# Power.net
KiCad netlist of a schematic drawn in Altium Designer
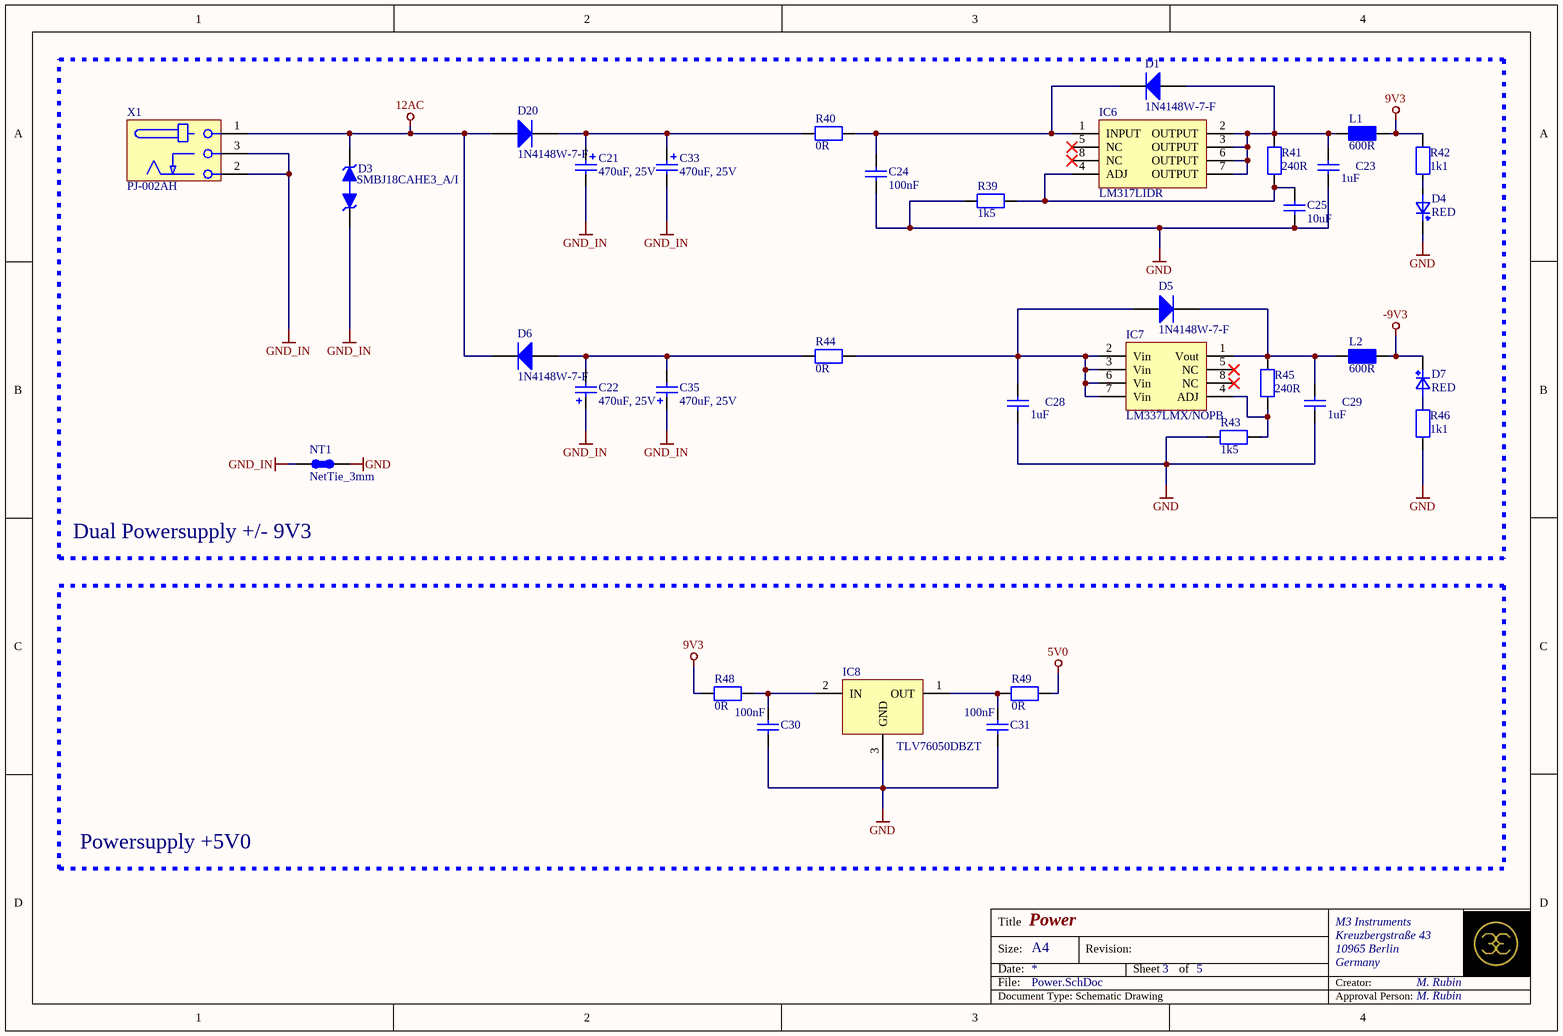
[diagram p0: Power.SchDoc]

(export (version "E")
  (design (tool "Eeschema 10.0.6"))
  (components
    (comp (ref "C21")
      (value "470uF, 25V")
      (footprint "WCAP-ATG8_D8H11.5")
      (description "WCAP-ATG8 Aluminum Electrolytic Capacitor, Radial, THT, D8xH11.5, 470uF, 25V")
      (fields
        (field (name "MANUFACTURER") "Wurth Elektronik")
        (field (name "MANUFACTURER PART NUMBER") "860010474013")
      )
      (libsource (lib "Caps") (part "CAP_470uF, 25V"))
    )
    (comp (ref "C22")
      (value "470uF, 25V")
      (footprint "WCAP-ATG8_D8H11.5")
      (description "WCAP-ATG8 Aluminum Electrolytic Capacitor, Radial, THT, D8xH11.5, 470uF, 25V")
      (fields
        (field (name "MANUFACTURER") "Wurth Elektronik")
        (field (name "MANUFACTURER PART NUMBER") "860010474013")
      )
      (libsource (lib "Caps") (part "CAP_470uF, 25V"))
    )
    (comp (ref "C23")
      (value "1uF")
      (footprint "CAPC2012X145N")
      (description "Multilayer Ceramic Capacitors MLCC - SMD/SMT, 1uF")
      (fields
        (field (name "MANUFACTURER") "Samsung Electro-Mechanics")
        (field (name "MANUFACTURER PART NUMBER") "CL21B105KBFNNNE")
      )
      (libsource (lib "Caps") (part "CAP_1uF_0805"))
    )
    (comp (ref "C24")
      (value "100nF")
      (footprint "CAPC1608X95N")
      (description "Multilayer Ceramic Capacitors MLCC - SMD/SMT, 100nF")
      (fields
        (field (name "MANUFACTURER") "YAGEO")
        (field (name "MANUFACTURER PART NUMBER") "CC0603KRX7R9BB104")
      )
      (libsource (lib "Caps") (part "CAP_100nF_0603"))
    )
    (comp (ref "C25")
      (value "10uF")
      (footprint "CAPC2012X145N")
      (description "Multilayer Ceramic Capacitors MLCC - SMD/SMT, 10uF")
      (fields
        (field (name "MANUFACTURER") "Samsung Electro-Mechanics")
        (field (name "MANUFACTURER PART NUMBER") "CL21A106KAYNNNE")
      )
      (libsource (lib "Caps") (part "CAP_10uF_0805"))
    )
    (comp (ref "C28")
      (value "1uF")
      (footprint "CAPC2012X145N")
      (description "Multilayer Ceramic Capacitors MLCC - SMD/SMT, 1uF")
      (fields
        (field (name "MANUFACTURER") "Samsung Electro-Mechanics")
        (field (name "MANUFACTURER PART NUMBER") "CL21B105KBFNNNE")
      )
      (libsource (lib "Caps") (part "CAP_1uF_0805"))
    )
    (comp (ref "C29")
      (value "1uF")
      (footprint "CAPC2012X145N")
      (description "Multilayer Ceramic Capacitors MLCC - SMD/SMT, 1uF")
      (fields
        (field (name "MANUFACTURER") "Samsung Electro-Mechanics")
        (field (name "MANUFACTURER PART NUMBER") "CL21B105KBFNNNE")
      )
      (libsource (lib "Caps") (part "CAP_1uF_0805"))
    )
    (comp (ref "C30")
      (value "100nF")
      (footprint "CAPC1608X95N")
      (description "Multilayer Ceramic Capacitors MLCC - SMD/SMT, 100nF")
      (fields
        (field (name "MANUFACTURER") "YAGEO")
        (field (name "MANUFACTURER PART NUMBER") "CC0603KRX7R9BB104")
      )
      (libsource (lib "Caps") (part "CAP_100nF_0603"))
    )
    (comp (ref "C31")
      (value "100nF")
      (footprint "CAPC1608X95N")
      (description "Multilayer Ceramic Capacitors MLCC - SMD/SMT, 100nF")
      (fields
        (field (name "MANUFACTURER") "YAGEO")
        (field (name "MANUFACTURER PART NUMBER") "CC0603KRX7R9BB104")
      )
      (libsource (lib "Caps") (part "CAP_100nF_0603"))
    )
    (comp (ref "C33")
      (value "470uF, 25V")
      (footprint "WCAP-ATG8_D8H11.5")
      (description "WCAP-ATG8 Aluminum Electrolytic Capacitor, Radial, THT, D8xH11.5, 470uF, 25V")
      (fields
        (field (name "MANUFACTURER") "Wurth Elektronik")
        (field (name "MANUFACTURER PART NUMBER") "860010474013")
      )
      (libsource (lib "Caps") (part "CAP_470uF, 25V"))
    )
    (comp (ref "C35")
      (value "470uF, 25V")
      (footprint "WCAP-ATG8_D8H11.5")
      (description "WCAP-ATG8 Aluminum Electrolytic Capacitor, Radial, THT, D8xH11.5, 470uF, 25V")
      (fields
        (field (name "MANUFACTURER") "Wurth Elektronik")
        (field (name "MANUFACTURER PART NUMBER") "860010474013")
      )
      (libsource (lib "Caps") (part "CAP_470uF, 25V"))
    )
    (comp (ref "D1")
      (value "1N4148W-7-F")
      (footprint "SOD-123")
      (description "Diodes - General Purpose, Power, Switching SURFACE MOUNT FAST SWITCHING DIODE 2A")
      (fields (field (name "MANUFACTURER") "Diodes Incorporated"))
      (libsource (lib "Diodes") (part "1N4148W-7-F"))
    )
    (comp (ref "D3")
      (value "SMBJ18CAHE3_A/I")
      (footprint "DIOM4336X24N")
      (description "ESD Suppressors / TVS Diodes 600W 18V 5% SMB (DO-214AA)")
      (fields (field (name "MANUFACTURER") "Vishay General Semiconductor"))
      (libsource (lib "Diodes") (part "DIO_SMBJ18CAHE3_A/I"))
    )
    (comp (ref "D4")
      (value "RED")
      (footprint "WL-SMCW_0805")
      (description "Standard LEDs - SMD WL-SMCW SMDMono TpVw Waterclr 0805 Red")
      (fields
        (field (name "MANUFACTURER") "Wurth Elektronik")
        (field (name "MANUFACTURER PART NUMBER") "150080RS75000")
      )
      (libsource (lib "Diodes") (part "LED_0805_RED_AK"))
    )
    (comp (ref "D5")
      (value "1N4148W-7-F")
      (footprint "SOD-123")
      (description "Diodes - General Purpose, Power, Switching SURFACE MOUNT FAST SWITCHING DIODE 2A")
      (fields (field (name "MANUFACTURER") "Diodes Incorporated"))
      (libsource (lib "Diodes") (part "1N4148W-7-F"))
    )
    (comp (ref "D6")
      (value "1N4148W-7-F")
      (footprint "SOD-123")
      (description "Diodes - General Purpose, Power, Switching SURFACE MOUNT FAST SWITCHING DIODE 2A")
      (fields (field (name "MANUFACTURER") "Diodes Incorporated"))
      (libsource (lib "Diodes") (part "1N4148W-7-F"))
    )
    (comp (ref "D7")
      (value "RED")
      (footprint "WL-SMCW_0805")
      (description "Standard LEDs - SMD WL-SMCW SMDMono TpVw Waterclr 0805 Red")
      (fields
        (field (name "MANUFACTURER") "Wurth Elektronik")
        (field (name "MANUFACTURER PART NUMBER") "150080RS75000")
      )
      (libsource (lib "Diodes") (part "LED_0805_RED_AK"))
    )
    (comp (ref "D20")
      (value "1N4148W-7-F")
      (footprint "SOD-123")
      (description "Diodes - General Purpose, Power, Switching SURFACE MOUNT FAST SWITCHING DIODE 2A")
      (fields (field (name "MANUFACTURER") "Diodes Incorporated"))
      (libsource (lib "Diodes") (part "1N4148W-7-F"))
    )
    (comp (ref "IC6")
      (value "LM317LIDR")
      (footprint "SOIC127P600X175-8N")
      (description "Linear Voltage Regulators")
      (fields (field (name "MANUFACTURER") "Texas Instruments"))
      (libsource (lib "ICs") (part "IC_LM317LIDR"))
    )
    (comp (ref "IC7")
      (value "LM337LMX/NOPB")
      (footprint "SOIC127P600X175-8N")
      (description "IC REG LIN POS ADJ 300MA SOT25")
      (fields (field (name "MANUFACTURER") "Texas Instruments"))
      (libsource (lib "ICs") (part "IC_LM337LMX/NOPB"))
    )
    (comp (ref "IC8")
      (value "TLV76050DBZT")
      (footprint "SOT95P280X135-3N_123")
      (description "PMIC - Spannungsregler - Linear Positiv Fest 1 Ausgang 100mA SOT-23-3")
      (fields (field (name "MANUFACTURER") "Texas Instruments"))
      (libsource (lib "ICs") (part "IC_TLV76050DBZT"))
    )
    (comp (ref "L1")
      (value "600R")
      (footprint "INDC2012X85N")
      (description "Ferrite Beads 0805 600 OHM")
      (fields
        (field (name "MANUFACTURER") "Murata Electronics")
        (field (name "MANUFACTURER PART NUMBER") "BLM21AG601SN1D")
      )
      (libsource (lib "Inductors") (part "FB_600R_600mA_0805"))
    )
    (comp (ref "L2")
      (value "600R")
      (footprint "INDC2012X85N")
      (description "Ferrite Beads 0805 600 OHM")
      (fields
        (field (name "MANUFACTURER") "Murata Electronics")
        (field (name "MANUFACTURER PART NUMBER") "BLM21AG601SN1D")
      )
      (libsource (lib "Inductors") (part "FB_600R_600mA_0805"))
    )
    (comp (ref "NT1")
      (value "NetTie_3mm")
      (footprint "NET_TIE_3MM")
      (description "3mm NetTie")
      (libsource (lib "MISC") (part "NetTie_3mm"))
    )
    (comp (ref "R39")
      (value "1k5")
      (footprint "RESC2012X70N")
      (description "Thick Film Resistors - SMD 1.5 kOhms 125 mW 0805 1% AEC-Q200")
      (fields
        (field (name "MANUFACTURER") "YAGEO")
        (field (name "MANUFACTURER PART NUMBER") "AC0805FR-071K5L")
      )
      (libsource (lib "Resistors") (part "RES_1k5_0805"))
    )
    (comp (ref "R40")
      (value "0R")
      (footprint "RESC2012X70N")
      (description "Thick Film Resistors - SMD 1/8watt ZEROohm Jumper")
      (fields
        (field (name "MANUFACTURER") "Vishay")
        (field (name "MANUFACTURER PART NUMBER") "CRCW08050000Z0EA")
      )
      (libsource (lib "Resistors") (part "RES_0R_0805"))
    )
    (comp (ref "R41")
      (value "240R")
      (footprint "RESC2012X70N")
      (description "Thick Film Resistors - SMD 1/8watt 240ohms 1%")
      (fields
        (field (name "MANUFACTURER") "Vishay / Dale")
        (field (name "MANUFACTURER PART NUMBER") "CRCW0805240RFKEA")
      )
      (libsource (lib "Resistors") (part "RES_240R_0805"))
    )
    (comp (ref "R42")
      (value "1k1")
      (footprint "RESC2012X70N")
      (description "Thick Film Resistors - SMD 1/8watt 1.1Kohms 1% 100ppm")
      (fields
        (field (name "MANUFACTURER") "Vishay / Dale")
        (field (name "MANUFACTURER PART NUMBER") "CRCW08051K10FKEA")
      )
      (libsource (lib "") (part "RES_1k1_0805_1"))
    )
    (comp (ref "R43")
      (value "1k5")
      (footprint "RESC2012X70N")
      (description "Thick Film Resistors - SMD 1.5 kOhms 125 mW 0805 1% AEC-Q200")
      (fields
        (field (name "MANUFACTURER") "YAGEO")
        (field (name "MANUFACTURER PART NUMBER") "AC0805FR-071K5L")
      )
      (libsource (lib "Resistors") (part "RES_1k5_0805"))
    )
    (comp (ref "R44")
      (value "0R")
      (footprint "RESC2012X70N")
      (description "Thick Film Resistors - SMD 1/8watt ZEROohm Jumper")
      (fields
        (field (name "MANUFACTURER") "Vishay")
        (field (name "MANUFACTURER PART NUMBER") "CRCW08050000Z0EA")
      )
      (libsource (lib "Resistors") (part "RES_0R_0805"))
    )
    (comp (ref "R45")
      (value "240R")
      (footprint "RESC2012X70N")
      (description "Thick Film Resistors - SMD 1/8watt 240ohms 1%")
      (fields
        (field (name "MANUFACTURER") "Vishay / Dale")
        (field (name "MANUFACTURER PART NUMBER") "CRCW0805240RFKEA")
      )
      (libsource (lib "Resistors") (part "RES_240R_0805"))
    )
    (comp (ref "R46")
      (value "1k1")
      (footprint "RESC2012X70N")
      (description "Thick Film Resistors - SMD 1/8watt 1.1Kohms 1% 100ppm")
      (fields
        (field (name "MANUFACTURER") "Vishay / Dale")
        (field (name "MANUFACTURER PART NUMBER") "CRCW08051K10FKEA")
      )
      (libsource (lib "Resistors") (part "RES_1k1_0805"))
    )
    (comp (ref "R48")
      (value "0R")
      (footprint "RESC2012X70N")
      (description "Thick Film Resistors - SMD 1/8watt ZEROohm Jumper")
      (fields
        (field (name "MANUFACTURER") "Vishay")
        (field (name "MANUFACTURER PART NUMBER") "CRCW08050000Z0EA")
      )
      (libsource (lib "Resistors") (part "RES_0R_0805"))
    )
    (comp (ref "R49")
      (value "0R")
      (footprint "RESC2012X70N")
      (description "Thick Film Resistors - SMD 1/8watt ZEROohm Jumper")
      (fields
        (field (name "MANUFACTURER") "Vishay")
        (field (name "MANUFACTURER PART NUMBER") "CRCW08050000Z0EA")
      )
      (libsource (lib "Resistors") (part "RES_0R_0805"))
    )
    (comp (ref "X1")
      (value "PJ-002AH")
      (footprint "PJ3L1400H110")
      (description "DC Power Connectors Power Jacks, Inside Contact Diameter 2mm, Outside Contact Diameter 6,5mm")
      (fields
        (field (name "MANUFACTURER") "CUI Devices")
        (field (name "LUMIRA PART NUMBER") "S-QMS-SPEC-32532")
      )
      (libsource (lib "_CONNECTORS") (part "PJ-002AH"))
    )
  )
  (nets
    (net (code "1") (name "-9V3") (class "Default")
      (node (ref "D7") (pin "K") (pinfunction "K_K") (pintype "passive"))
      (node (ref "L2") (pin "2") (pinfunction "2_2") (pintype "passive"))
    )
    (net (code "2") (name "5V0") (class "Default")
      (node (ref "R49") (pin "2") (pinfunction "2_2") (pintype "passive"))
    )
    (net (code "3") (name "9V3") (class "Default")
      (node (ref "L1") (pin "2") (pinfunction "2_2") (pintype "passive"))
      (node (ref "R42") (pin "2") (pinfunction "2_2") (pintype "passive"))
      (node (ref "R48") (pin "1") (pinfunction "1_1") (pintype "passive"))
    )
    (net (code "4") (name "12AC") (class "Default")
      (node (ref "D20") (pin "1") (pinfunction "A_1") (pintype "passive"))
      (node (ref "D3") (pin "K") (pinfunction "K_K") (pintype "passive"))
      (node (ref "D6") (pin "2") (pinfunction "K_2") (pintype "passive"))
      (node (ref "X1") (pin "1") (pinfunction "1_1") (pintype "passive"))
    )
    (net (code "5") (name "GND") (class "Default")
      (node (ref "C23") (pin "1") (pinfunction "1_1") (pintype "passive"))
      (node (ref "C24") (pin "1") (pinfunction "1_1") (pintype "passive"))
      (node (ref "C25") (pin "1") (pinfunction "1_1") (pintype "passive"))
      (node (ref "C28") (pin "1") (pinfunction "1_1") (pintype "passive"))
      (node (ref "C29") (pin "1") (pinfunction "1_1") (pintype "passive"))
      (node (ref "C30") (pin "1") (pinfunction "1_1") (pintype "passive"))
      (node (ref "C31") (pin "1") (pinfunction "1_1") (pintype "passive"))
      (node (ref "D4") (pin "K") (pinfunction "K_K") (pintype "passive"))
      (node (ref "IC8") (pin "3") (pinfunction "GND_3") (pintype "power_in"))
      (node (ref "NT1") (pin "1") (pinfunction "1_1") (pintype "passive"))
      (node (ref "R39") (pin "1") (pinfunction "1_1") (pintype "passive"))
      (node (ref "R43") (pin "1") (pinfunction "1_1") (pintype "passive"))
      (node (ref "R46") (pin "2") (pinfunction "2_2") (pintype "passive"))
    )
    (net (code "6") (name "GND_IN") (class "Default")
      (node (ref "C21") (pin "N") (pinfunction "N_N") (pintype "passive"))
      (node (ref "C22") (pin "P") (pinfunction "P_P") (pintype "passive"))
      (node (ref "C33") (pin "N") (pinfunction "N_N") (pintype "passive"))
      (node (ref "C35") (pin "P") (pinfunction "P_P") (pintype "passive"))
      (node (ref "D3") (pin "A") (pinfunction "A_A") (pintype "passive"))
      (node (ref "NT1") (pin "2") (pinfunction "2_2") (pintype "passive"))
      (node (ref "X1") (pin "2") (pinfunction "2_2") (pintype "passive"))
      (node (ref "X1") (pin "3") (pinfunction "3_3") (pintype "passive"))
    )
    (net (code "7") (name "Net-(D1-A)") (class "Default")
      (node (ref "C23") (pin "2") (pinfunction "2_2") (pintype "passive"))
      (node (ref "D1") (pin "1") (pinfunction "A_1") (pintype "passive"))
      (node (ref "IC6") (pin "2") (pinfunction "OUTPUT_2") (pintype "power_in"))
      (node (ref "IC6") (pin "3") (pinfunction "OUTPUT_3") (pintype "power_in"))
      (node (ref "IC6") (pin "6") (pinfunction "OUTPUT_6") (pintype "power_in"))
      (node (ref "IC6") (pin "7") (pinfunction "OUTPUT_7") (pintype "power_in"))
      (node (ref "L1") (pin "1") (pinfunction "1_1") (pintype "passive"))
      (node (ref "R41") (pin "2") (pinfunction "2_2") (pintype "passive"))
    )
    (net (code "8") (name "Net-(D1-K)") (class "Default")
      (node (ref "C24") (pin "2") (pinfunction "2_2") (pintype "passive"))
      (node (ref "D1") (pin "2") (pinfunction "K_2") (pintype "passive"))
      (node (ref "IC6") (pin "1") (pinfunction "INPUT_1") (pintype "passive"))
      (node (ref "R40") (pin "2") (pinfunction "2_2") (pintype "passive"))
    )
    (net (code "9") (name "Net-(D4-PadA)") (class "Default")
      (node (ref "D4") (pin "A") (pinfunction "A_A") (pintype "passive"))
      (node (ref "R42") (pin "1") (pinfunction "1_1") (pintype "passive"))
    )
    (net (code "10") (name "Net-(D5-A)") (class "Default")
      (node (ref "C28") (pin "2") (pinfunction "2_2") (pintype "passive"))
      (node (ref "D5") (pin "1") (pinfunction "A_1") (pintype "passive"))
      (node (ref "IC7") (pin "2") (pinfunction "Vin_2") (pintype "power_in"))
      (node (ref "IC7") (pin "3") (pinfunction "Vin_3") (pintype "power_in"))
      (node (ref "IC7") (pin "6") (pinfunction "Vin_6") (pintype "power_in"))
      (node (ref "IC7") (pin "7") (pinfunction "Vin_7") (pintype "power_in"))
      (node (ref "R44") (pin "2") (pinfunction "2_2") (pintype "passive"))
    )
    (net (code "11") (name "Net-(D5-K)") (class "Default")
      (node (ref "C29") (pin "2") (pinfunction "2_2") (pintype "passive"))
      (node (ref "D5") (pin "2") (pinfunction "K_2") (pintype "passive"))
      (node (ref "IC7") (pin "1") (pinfunction "Vout_1") (pintype "passive"))
      (node (ref "L2") (pin "1") (pinfunction "1_1") (pintype "passive"))
      (node (ref "R45") (pin "2") (pinfunction "2_2") (pintype "passive"))
    )
    (net (code "12") (name "Net-(D6-A)") (class "Default")
      (node (ref "C22") (pin "N") (pinfunction "N_N") (pintype "passive"))
      (node (ref "C35") (pin "N") (pinfunction "N_N") (pintype "passive"))
      (node (ref "D6") (pin "1") (pinfunction "A_1") (pintype "passive"))
      (node (ref "R44") (pin "1") (pinfunction "1_1") (pintype "passive"))
    )
    (net (code "13") (name "Net-(D7-PadA)") (class "Default")
      (node (ref "D7") (pin "A") (pinfunction "A_A") (pintype "passive"))
      (node (ref "R46") (pin "1") (pinfunction "1_1") (pintype "passive"))
    )
    (net (code "14") (name "Net-(D20-K)") (class "Default")
      (node (ref "C21") (pin "P") (pinfunction "P_P") (pintype "passive"))
      (node (ref "C33") (pin "P") (pinfunction "P_P") (pintype "passive"))
      (node (ref "D20") (pin "2") (pinfunction "K_2") (pintype "passive"))
      (node (ref "R40") (pin "1") (pinfunction "1_1") (pintype "passive"))
    )
    (net (code "15") (name "Net-(IC6-ADJ)") (class "Default")
      (node (ref "C25") (pin "2") (pinfunction "2_2") (pintype "passive"))
      (node (ref "IC6") (pin "4") (pinfunction "ADJ_4") (pintype "power_in"))
      (node (ref "R39") (pin "2") (pinfunction "2_2") (pintype "passive"))
      (node (ref "R41") (pin "1") (pinfunction "1_1") (pintype "passive"))
    )
    (net (code "16") (name "Net-(IC7-ADJ)") (class "Default")
      (node (ref "IC7") (pin "4") (pinfunction "ADJ_4") (pintype "power_in"))
      (node (ref "R43") (pin "2") (pinfunction "2_2") (pintype "passive"))
      (node (ref "R45") (pin "1") (pinfunction "1_1") (pintype "passive"))
    )
    (net (code "17") (name "Net-(IC8-IN)") (class "Default")
      (node (ref "C30") (pin "2") (pinfunction "2_2") (pintype "passive"))
      (node (ref "IC8") (pin "2") (pinfunction "IN_2") (pintype "power_in"))
      (node (ref "R48") (pin "2") (pinfunction "2_2") (pintype "passive"))
    )
    (net (code "18") (name "Net-(IC8-OUT)") (class "Default")
      (node (ref "C31") (pin "2") (pinfunction "2_2") (pintype "passive"))
      (node (ref "IC8") (pin "1") (pinfunction "OUT_1") (pintype "passive"))
      (node (ref "R49") (pin "1") (pinfunction "1_1") (pintype "passive"))
    )
    (net (code "19") (name "unconnected-(IC6-NC-Pad5)") (class "Default")
      (node (ref "IC6") (pin "5") (pinfunction "NC_5") (pintype "power_in+no_connect"))
    )
    (net (code "20") (name "unconnected-(IC6-NC-Pad8)") (class "Default")
      (node (ref "IC6") (pin "8") (pinfunction "NC_8") (pintype "power_in+no_connect"))
    )
    (net (code "21") (name "unconnected-(IC7-NC-Pad5)") (class "Default")
      (node (ref "IC7") (pin "5") (pinfunction "NC_5") (pintype "power_in+no_connect"))
    )
    (net (code "22") (name "unconnected-(IC7-NC-Pad8)") (class "Default")
      (node (ref "IC7") (pin "8") (pinfunction "NC_8") (pintype "power_in+no_connect"))
    )
  )
)
